# Memory.net
KiCad netlist of a schematic drawn in Altium Designer
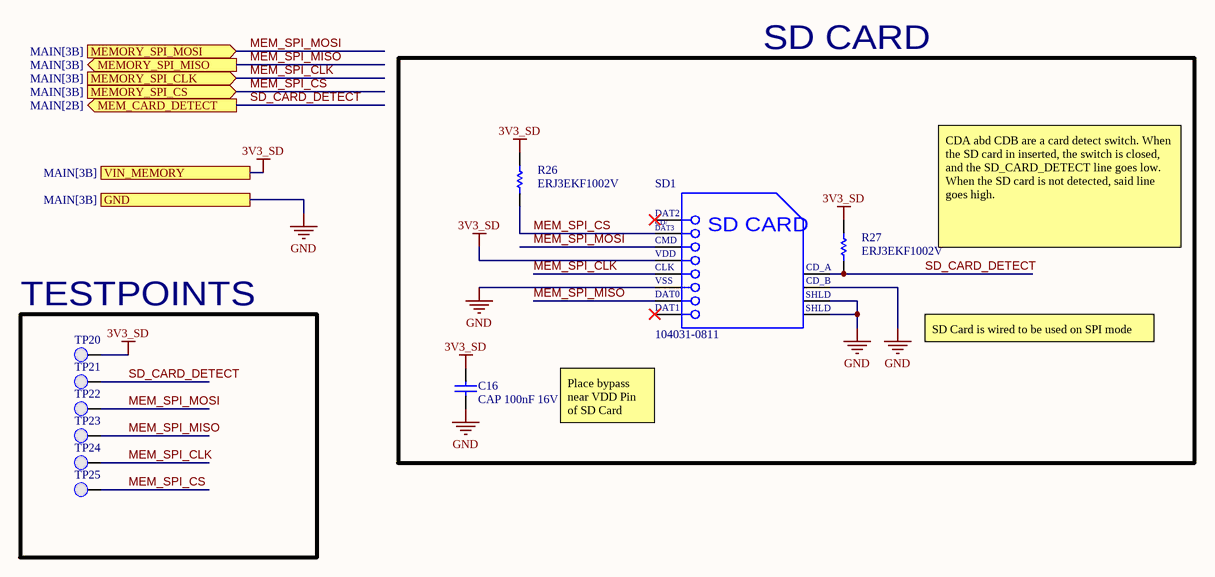
[diagram p0: Memory.SchDoc]

(export (version "E")
  (design (tool "Eeschema 10.0.6"))
  (components
    (comp (ref "C16")
      (value "CAP 100nF 16V 0603(1608)")
      (footprint "CAPC0603(1608)100_N")
      (description "CAP 100nF 16V ±10% 0603 (1608 Metric) Thickness 1mm SMD")
      (fields (field (name "TOLERANCE") "Â±10%"))
      (libsource (lib "Altium Content Vault") (part "CAP"))
    )
    (comp (ref "R26")
      (value "ERJ3EKF1002V")
      (footprint "RESC1609X55X30LL15T15")
      (description "Chip Resistor, 10 KOhm, +/- 1%, 0.1 W, -55 to 155 degC, 0603 (1608 Metric), RoHS, Tape and Reel")
      (fields (field (name "TOLERANCE") "1%") (field (name "MANUFACTURER") "Panasonic"))
      (libsource (lib "Altium Content Vault") (part "RES-2"))
    )
    (comp (ref "R27")
      (value "ERJ3EKF1002V")
      (footprint "RESC1609X55X30LL15T15")
      (description "Chip Resistor, 10 KOhm, +/- 1%, 0.1 W, -55 to 155 degC, 0603 (1608 Metric), RoHS, Tape and Reel")
      (fields (field (name "TOLERANCE") "1%") (field (name "MANUFACTURER") "Panasonic"))
      (libsource (lib "Altium Content Vault") (part "RES-2"))
    )
    (comp (ref "SD1")
      (value "104031-0811")
      (footprint "MOLX-104031-0811_V")
      (description "Micro SD Card, RA, -25 to 85 degC, 8-Pin SMD, RoHS, Tape and Reel")
      (fields (field (name "MANUFACTURER") "Molex"))
      (libsource (lib "Altium Content Vault") (part "CN-SD-8-2SW-2S"))
    )
    (comp (ref "TP20")
      (value "0.1\" Pad")
      (footprint "PCBComponent")
      (libsource (lib "Components - 12.02.20 - 18.05") (part "0.1{dblquote} Pad-A.4"))
    )
    (comp (ref "TP21")
      (value "0.1\" Pad")
      (footprint "PCBComponent")
      (libsource (lib "Components - 12.02.20 - 18.05") (part "0.1{dblquote} Pad-A.4"))
    )
    (comp (ref "TP22")
      (value "0.1\" Pad")
      (footprint "PCBComponent")
      (libsource (lib "Components - 12.02.20 - 18.05") (part "0.1{dblquote} Pad-A.4"))
    )
    (comp (ref "TP23")
      (value "0.1\" Pad")
      (footprint "PCBComponent")
      (libsource (lib "Components - 12.02.20 - 18.05") (part "0.1{dblquote} Pad-A.4"))
    )
    (comp (ref "TP24")
      (value "0.1\" Pad")
      (footprint "PCBComponent")
      (libsource (lib "Components - 12.02.20 - 18.05") (part "0.1{dblquote} Pad-A.4"))
    )
    (comp (ref "TP25")
      (value "0.1\" Pad")
      (footprint "PCBComponent")
      (libsource (lib "Components - 12.02.20 - 18.05") (part "0.1{dblquote} Pad-A.4"))
    )
  )
  (nets
    (net (code "1") (name "/MEM_SPI_CLK") (class "Default")
      (node (ref "SD1") (pin "5") (pinfunction "CLK_5") (pintype "passive"))
      (node (ref "TP24") (pin "1") (pinfunction "PAD_1") (pintype "passive"))
    )
    (net (code "2") (name "/MEM_SPI_CS") (class "Default")
      (node (ref "R26") (pin "1") (pinfunction "1_1") (pintype "passive"))
      (node (ref "SD1") (pin "2") (pinfunction "CMD_2") (pintype "passive"))
      (node (ref "TP25") (pin "1") (pinfunction "PAD_1") (pintype "passive"))
    )
    (net (code "3") (name "/MEM_SPI_MISO") (class "Default")
      (node (ref "SD1") (pin "7") (pinfunction "DAT0_7") (pintype "passive"))
      (node (ref "TP23") (pin "1") (pinfunction "PAD_1") (pintype "passive"))
    )
    (net (code "4") (name "/MEM_SPI_MOSI") (class "Default")
      (node (ref "SD1") (pin "3") (pinfunction "VSS1_3") (pintype "passive"))
      (node (ref "TP22") (pin "1") (pinfunction "PAD_1") (pintype "passive"))
    )
    (net (code "5") (name "/SD_CARD_DETECT") (class "Default")
      (node (ref "R27") (pin "1") (pinfunction "1_1") (pintype "passive"))
      (node (ref "SD1") (pin "9") (pinfunction "CD_A_9") (pintype "passive"))
      (node (ref "TP21") (pin "1") (pinfunction "PAD_1") (pintype "passive"))
    )
    (net (code "6") (name "3V3_SD") (class "Default")
      (node (ref "C16") (pin "2") (pinfunction "2_2") (pintype "passive"))
      (node (ref "R26") (pin "2") (pinfunction "2_2") (pintype "passive"))
      (node (ref "R27") (pin "2") (pinfunction "2_2") (pintype "passive"))
      (node (ref "SD1") (pin "4") (pinfunction "VDD_4") (pintype "passive"))
      (node (ref "TP20") (pin "1") (pinfunction "PAD_1") (pintype "passive"))
    )
    (net (code "7") (name "GND") (class "Default")
      (node (ref "C16") (pin "1") (pinfunction "1_1") (pintype "passive"))
      (node (ref "SD1") (pin "10") (pinfunction "CD_B_10") (pintype "passive"))
      (node (ref "SD1") (pin "11") (pinfunction "SHLD1_11") (pintype "passive"))
      (node (ref "SD1") (pin "12") (pinfunction "SHLD2_12") (pintype "passive"))
      (node (ref "SD1") (pin "6") (pinfunction "VSS2_6") (pintype "passive"))
    )
    (net (code "8") (name "unconnected-(SD1-CD{slash}DAT3-Pad1)") (class "Default")
      (node (ref "SD1") (pin "1") (pinfunction "CD/DAT3_1") (pintype "passive+no_connect"))
    )
    (net (code "9") (name "unconnected-(SD1-DAT1-Pad8)") (class "Default")
      (node (ref "SD1") (pin "8") (pinfunction "DAT1_8") (pintype "passive+no_connect"))
    )
  )
)
